# amp-LNA-BFP740Fxxx.net
KiCad netlist of a schematic drawn in EAGLE
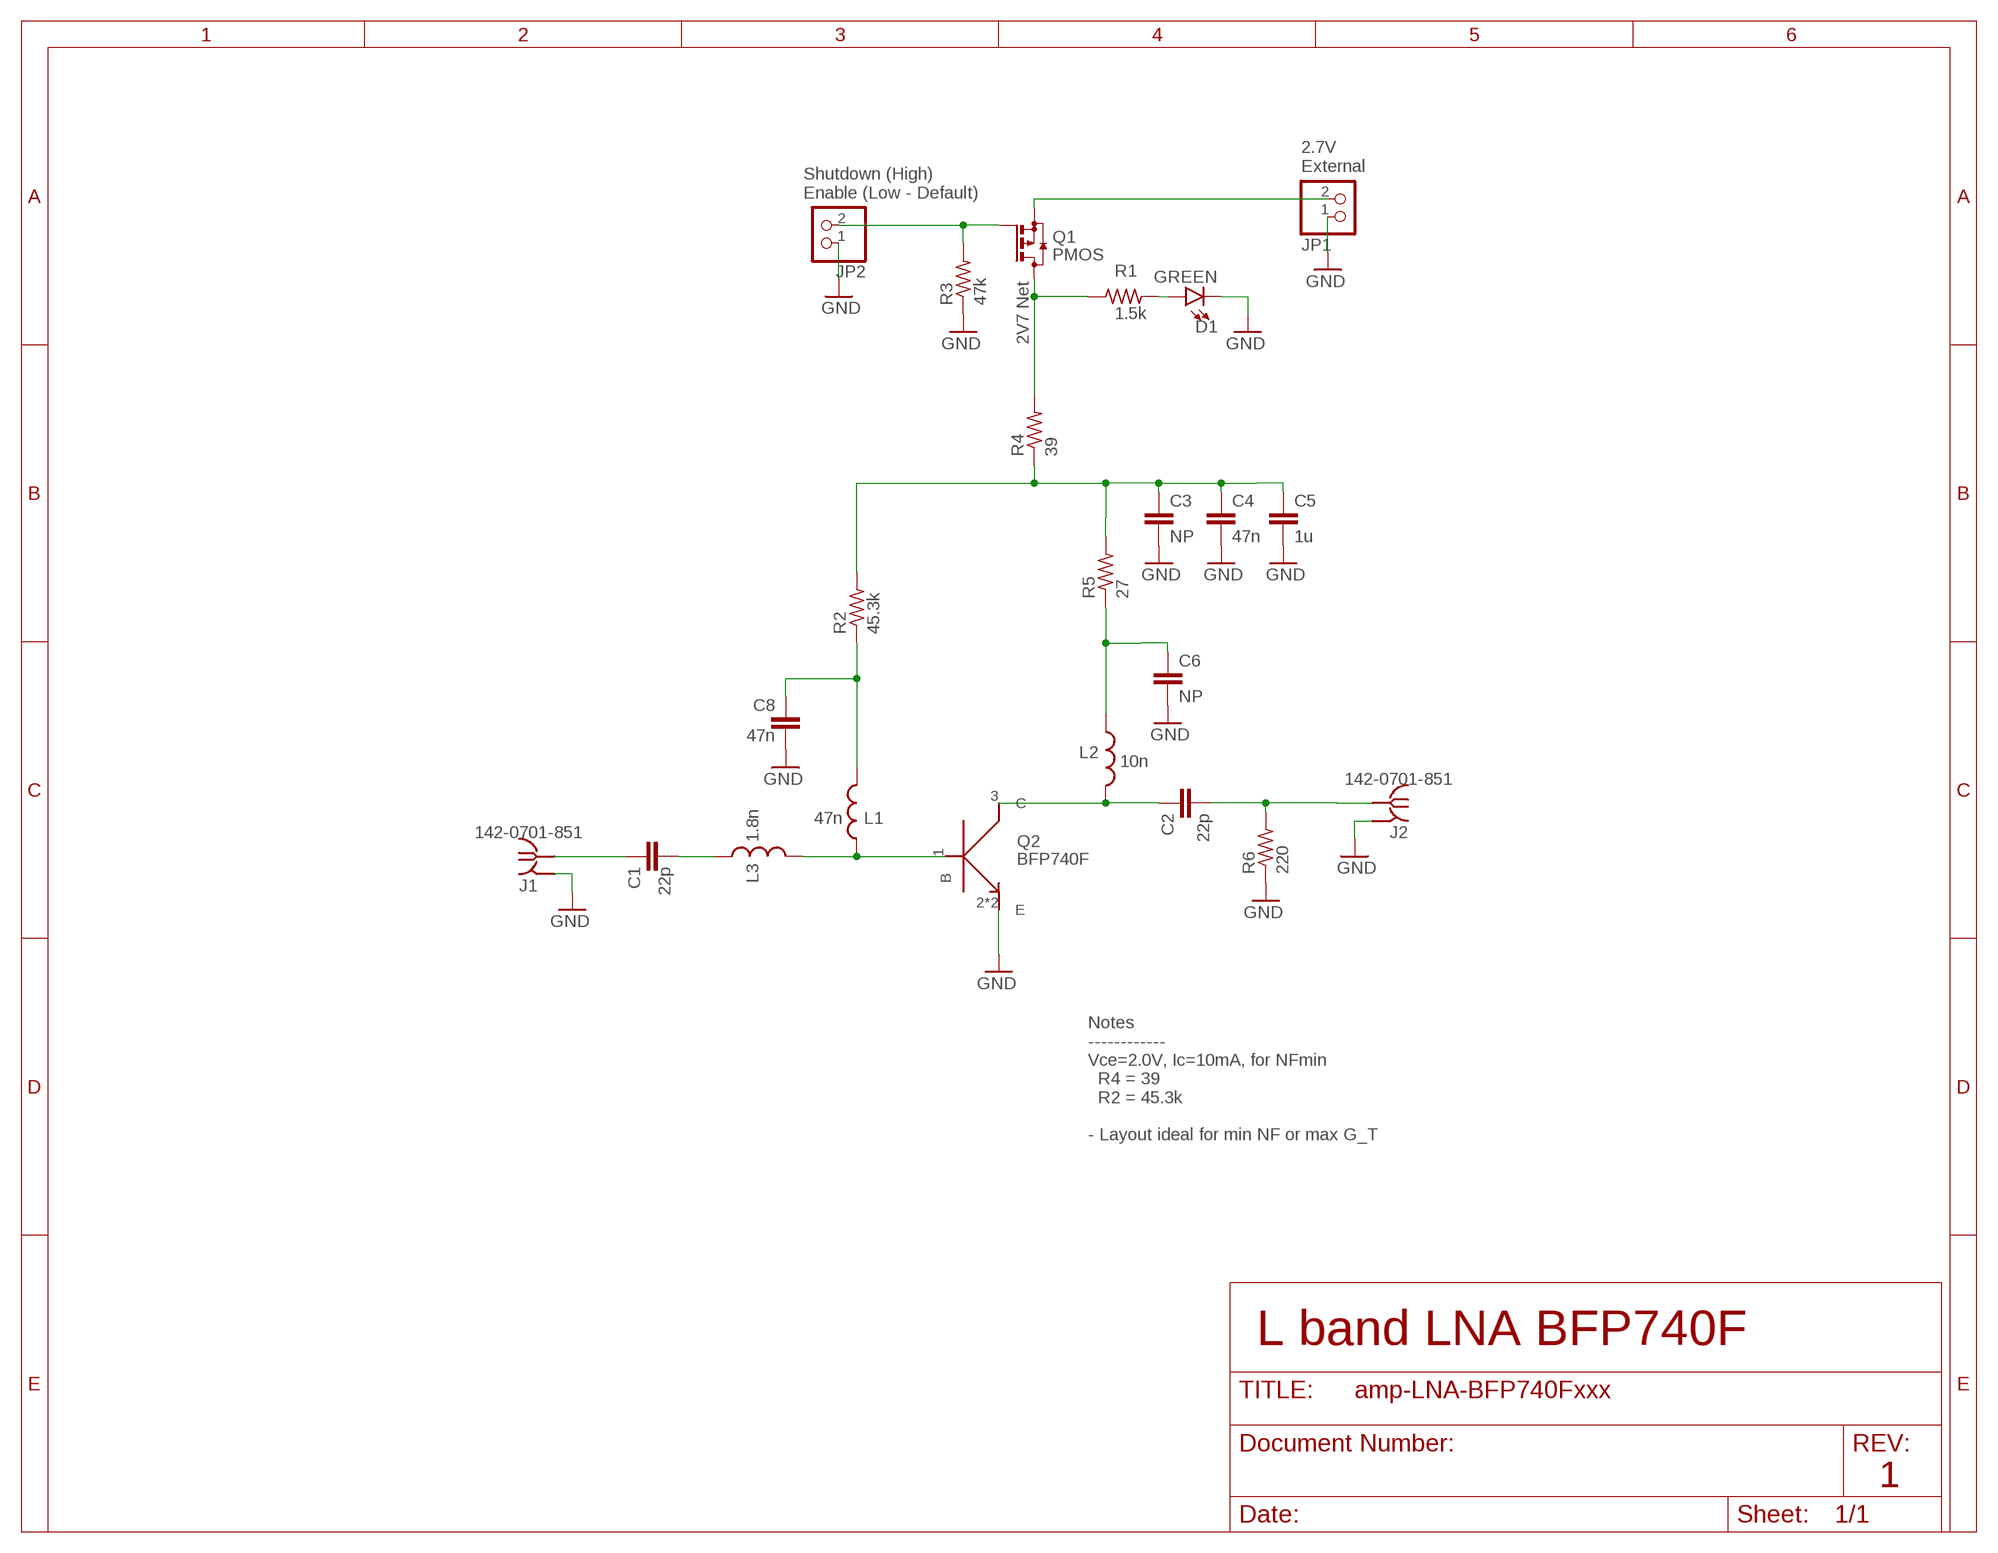
[diagram p0: schematic, sheet 1]

(export (version "E")
  (design (tool "Eeschema 10.0.6"))
  (components
    (comp (ref "C1")
      (value "22p")
      (footprint "eagle-import:.0402-C-NOSILK")
      (libsource (lib "eagle-import") (part "C-EU0402-C-NOSILK"))
    )
    (comp (ref "C2")
      (value "22p")
      (footprint "eagle-import:.0402-C-NOSILK")
      (libsource (lib "eagle-import") (part "C-EU0402-C-NOSILK"))
    )
    (comp (ref "C3")
      (value "NP")
      (footprint "eagle-import:.0603-C-NOSILK")
      (libsource (lib "eagle-import") (part "C-EU0603-C-NOSILK"))
    )
    (comp (ref "C4")
      (value "47n")
      (footprint "eagle-import:.0603-C-NOSILK")
      (libsource (lib "eagle-import") (part "C-EU0603-C-NOSILK"))
    )
    (comp (ref "C5")
      (value "1u")
      (footprint "eagle-import:.0603-C-NOSILK")
      (libsource (lib "eagle-import") (part "C-EU0603-C-NOSILK"))
    )
    (comp (ref "C6")
      (value "NP")
      (footprint "eagle-import:.0402-B-NOSILK")
      (libsource (lib "eagle-import") (part "C-EU0402-B-NOSILK"))
    )
    (comp (ref "C8")
      (value "47n")
      (footprint "eagle-import:.0603-C-NOSILK")
      (libsource (lib "eagle-import") (part "C-EU0603-C-NOSILK"))
    )
    (comp (ref "D1")
      (value "GREEN")
      (footprint "eagle-import:LED-0603")
      (libsource (lib "eagle-import") (part "LED-GREEN0603"))
    )
    (comp (ref "J1")
      (value "142-0701-851")
      (footprint "eagle-import:142-0701-851")
      (libsource (lib "eagle-import") (part "142-0701-851"))
    )
    (comp (ref "J2")
      (value "142-0701-851")
      (footprint "eagle-import:142-0701-851")
      (libsource (lib "eagle-import") (part "142-0701-851"))
    )
    (comp (ref "JP1")
      (value "PINHD-1X2")
      (footprint "eagle-import:1X02")
      (libsource (lib "eagle-import") (part "PINHD-1X2"))
    )
    (comp (ref "JP2")
      (value "PINHD-1X2")
      (footprint "eagle-import:1X02")
      (libsource (lib "eagle-import") (part "PINHD-1X2"))
    )
    (comp (ref "L1")
      (value "47n")
      (footprint "eagle-import:.0603-C-NOSILK")
      (libsource (lib "eagle-import") (part "L-US0603-C-NOSILK"))
    )
    (comp (ref "L2")
      (value "10n")
      (footprint "eagle-import:.0603-C-NOSILK")
      (libsource (lib "eagle-import") (part "L-US0603-C-NOSILK"))
    )
    (comp (ref "L3")
      (value "1.8n")
      (footprint "eagle-import:.0402-C-NOSILK")
      (libsource (lib "eagle-import") (part "L-US0402-C-NOSILK"))
    )
    (comp (ref "Q1")
      (value "PMOS")
      (footprint "eagle-import:SOT23")
      (libsource (lib "eagle-import") (part "BSS84"))
    )
    (comp (ref "Q2")
      (value "BFP740F")
      (footprint "eagle-import:TSFP4")
      (libsource (lib "eagle-import") (part "BFPXXXF"))
    )
    (comp (ref "R1")
      (value "1.5k")
      (footprint "eagle-import:.0603-C-NOSILK")
      (libsource (lib "eagle-import") (part "R-US_0603-C-NOSILK"))
    )
    (comp (ref "R2")
      (value "45.3k")
      (footprint "eagle-import:.0603-C-NOSILK")
      (libsource (lib "eagle-import") (part "R-US_0603-C-NOSILK"))
    )
    (comp (ref "R3")
      (value "47k")
      (footprint "eagle-import:.0402-B-NOSILK")
      (libsource (lib "eagle-import") (part "R-US_0402-B-NOSILK"))
    )
    (comp (ref "R4")
      (value "39")
      (footprint "eagle-import:.0603-C-NOSILK")
      (libsource (lib "eagle-import") (part "R-US_0603-C-NOSILK"))
    )
    (comp (ref "R5")
      (value "27")
      (footprint "eagle-import:.0603-C-NOSILK")
      (libsource (lib "eagle-import") (part "R-US_0603-C-NOSILK"))
    )
    (comp (ref "R6")
      (value "220")
      (footprint "eagle-import:.0603-C-NOSILK")
      (libsource (lib "eagle-import") (part "R-US_0603-C-NOSILK"))
    )
  )
  (nets
    (net (code "1") (name "GND") (class "Default")
      (node (ref "C3") (pin "2") (pinfunction "2_2") (pintype "passive"))
      (node (ref "C4") (pin "2") (pinfunction "2_2") (pintype "passive"))
      (node (ref "C5") (pin "2") (pinfunction "2_2") (pintype "passive"))
      (node (ref "C6") (pin "2") (pinfunction "2_2") (pintype "passive"))
      (node (ref "C8") (pin "2") (pinfunction "2_2") (pintype "passive"))
      (node (ref "D1") (pin "C") (pinfunction "C_C") (pintype "passive"))
      (node (ref "J1") (pin "GND1") (pinfunction "GND_GND1") (pintype "bidirectional"))
      (node (ref "J1") (pin "GND2") (pinfunction "GND_GND2") (pintype "bidirectional"))
      (node (ref "J1") (pin "GND3") (pinfunction "GND_GND3") (pintype "bidirectional"))
      (node (ref "J1") (pin "GND4") (pinfunction "GND_GND4") (pintype "bidirectional"))
      (node (ref "J2") (pin "GND1") (pinfunction "GND_GND1") (pintype "bidirectional"))
      (node (ref "J2") (pin "GND2") (pinfunction "GND_GND2") (pintype "bidirectional"))
      (node (ref "J2") (pin "GND3") (pinfunction "GND_GND3") (pintype "bidirectional"))
      (node (ref "J2") (pin "GND4") (pinfunction "GND_GND4") (pintype "bidirectional"))
      (node (ref "JP1") (pin "1") (pinfunction "1_1") (pintype "passive"))
      (node (ref "JP2") (pin "1") (pinfunction "1_1") (pintype "passive"))
      (node (ref "Q2") (pin "2") (pinfunction "E_2") (pintype "power_in"))
      (node (ref "Q2") (pin "4") (pinfunction "E_4") (pintype "power_in"))
      (node (ref "R3") (pin "1") (pinfunction "1_1") (pintype "passive"))
      (node (ref "R6") (pin "1") (pinfunction "1_1") (pintype "passive"))
    )
    (net (code "2") (name "Net-(C1-Pad2)") (class "Default")
      (node (ref "C1") (pin "2") (pinfunction "2_2") (pintype "passive"))
      (node (ref "L3") (pin "1") (pinfunction "1_1") (pintype "passive"))
    )
    (net (code "3") (name "Net-(C3-Pad1)") (class "Default")
      (node (ref "C3") (pin "1") (pinfunction "1_1") (pintype "passive"))
      (node (ref "C4") (pin "1") (pinfunction "1_1") (pintype "passive"))
      (node (ref "C5") (pin "1") (pinfunction "1_1") (pintype "passive"))
      (node (ref "R2") (pin "2") (pinfunction "2_2") (pintype "passive"))
      (node (ref "R4") (pin "1") (pinfunction "1_1") (pintype "passive"))
      (node (ref "R5") (pin "2") (pinfunction "2_2") (pintype "passive"))
    )
    (net (code "4") (name "Net-(C6-Pad1)") (class "Default")
      (node (ref "C6") (pin "1") (pinfunction "1_1") (pintype "passive"))
      (node (ref "L2") (pin "1") (pinfunction "1_1") (pintype "passive"))
      (node (ref "R5") (pin "1") (pinfunction "1_1") (pintype "passive"))
    )
    (net (code "5") (name "Net-(C8-Pad1)") (class "Default")
      (node (ref "C8") (pin "1") (pinfunction "1_1") (pintype "passive"))
      (node (ref "L1") (pin "2") (pinfunction "2_2") (pintype "passive"))
      (node (ref "R2") (pin "1") (pinfunction "1_1") (pintype "passive"))
    )
    (net (code "6") (name "Net-(D1-PadA)") (class "Default")
      (node (ref "D1") (pin "A") (pinfunction "A_A") (pintype "passive"))
      (node (ref "R1") (pin "2") (pinfunction "2_2") (pintype "passive"))
    )
    (net (code "7") (name "Net-(J1-RF)") (class "Default")
      (node (ref "C1") (pin "1") (pinfunction "1_1") (pintype "passive"))
      (node (ref "J1") (pin "RF1") (pinfunction "RF_RF1") (pintype "bidirectional"))
    )
    (net (code "8") (name "Net-(J2-RF)") (class "Default")
      (node (ref "C2") (pin "2") (pinfunction "2_2") (pintype "passive"))
      (node (ref "J2") (pin "RF1") (pinfunction "RF_RF1") (pintype "bidirectional"))
      (node (ref "R6") (pin "2") (pinfunction "2_2") (pintype "passive"))
    )
    (net (code "9") (name "Net-(Q1-D)") (class "Default")
      (node (ref "Q1") (pin "3") (pinfunction "D_3") (pintype "passive"))
      (node (ref "R1") (pin "1") (pinfunction "1_1") (pintype "passive"))
      (node (ref "R4") (pin "2") (pinfunction "2_2") (pintype "passive"))
    )
    (net (code "10") (name "Net-(Q1-G)") (class "Default")
      (node (ref "JP2") (pin "2") (pinfunction "2_2") (pintype "passive"))
      (node (ref "Q1") (pin "1") (pinfunction "G_1") (pintype "passive"))
      (node (ref "R3") (pin "2") (pinfunction "2_2") (pintype "passive"))
    )
    (net (code "11") (name "Net-(Q1-S)") (class "Default")
      (node (ref "JP1") (pin "2") (pinfunction "2_2") (pintype "passive"))
      (node (ref "Q1") (pin "2") (pinfunction "S_2") (pintype "passive"))
    )
    (net (code "12") (name "Net-(Q2-B)") (class "Default")
      (node (ref "L1") (pin "1") (pinfunction "1_1") (pintype "passive"))
      (node (ref "L3") (pin "2") (pinfunction "2_2") (pintype "passive"))
      (node (ref "Q2") (pin "1") (pinfunction "B_1") (pintype "input"))
    )
    (net (code "13") (name "Net-(Q2-C)") (class "Default")
      (node (ref "C2") (pin "1") (pinfunction "1_1") (pintype "passive"))
      (node (ref "L2") (pin "2") (pinfunction "2_2") (pintype "passive"))
      (node (ref "Q2") (pin "3") (pinfunction "C_3") (pintype "output"))
    )
  )
)
